# Sheet1.net
KiCad netlist of a schematic drawn in Altium Designer
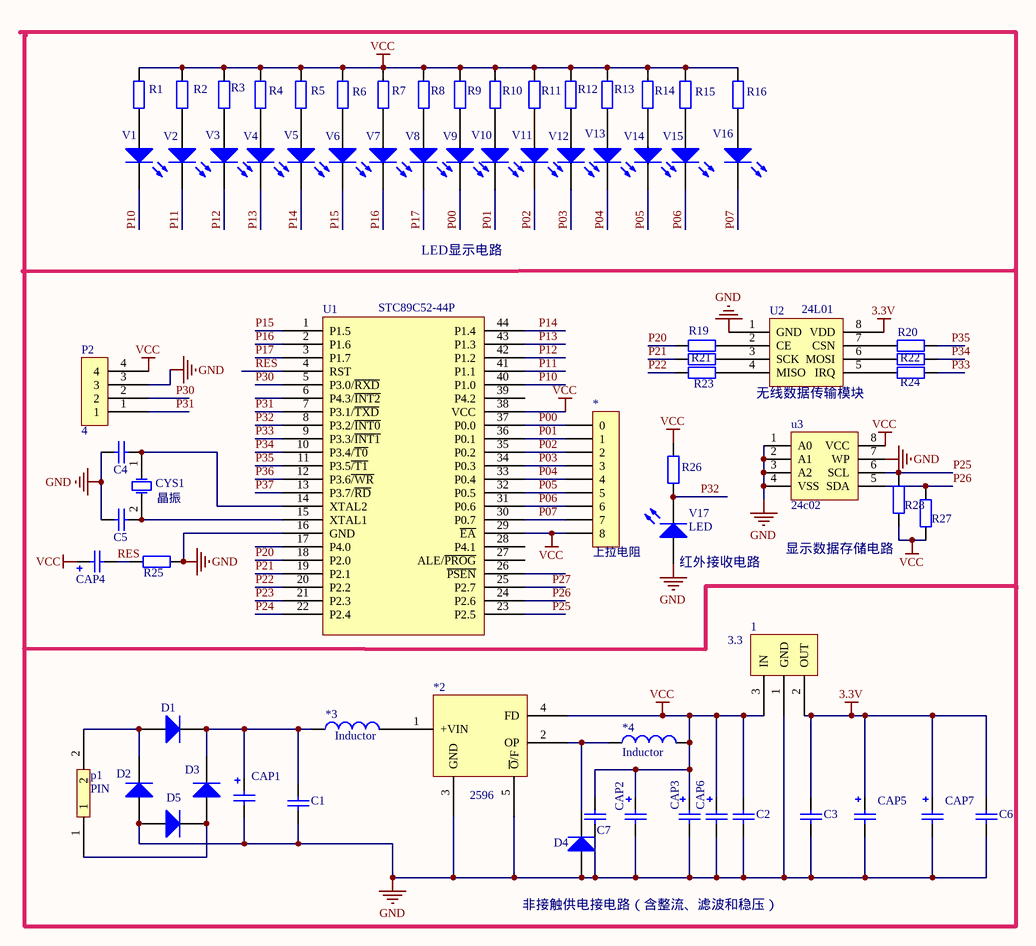
[diagram p0: Sheet1.SchDoc]

(export (version "E")
  (design (tool "Eeschema 10.0.6"))
  (components
    (comp (ref "*") (value "上拉电阻") (footprint "上拉电阻") (libsource (lib "标准封装") (part "上拉电阻")))
    (comp (ref "*2") (value "2596") (footprint "LM2596-P") (libsource (lib "标准封装") (part "2596")))
    (comp (ref "*3") (value "Inductor") (footprint "PIN") (libsource (lib "标准封装") (part "Inductor")))
    (comp (ref "*4") (value "Inductor") (footprint "PIN") (libsource (lib "标准封装") (part "Inductor")))
    (comp (ref "1") (value "3.3") (footprint "3.3") (libsource (lib "标准封装") (part "3.3")))
    (comp (ref "C1") (value "Cap") (footprint "RES") (libsource (lib "标准封装") (part "Cap")))
    (comp (ref "C2") (value "Cap") (footprint "C - duplicate") (libsource (lib "标准封装") (part "Cap")))
    (comp (ref "C3") (value "Cap") (footprint "C - duplicate") (libsource (lib "标准封装") (part "Cap")))
    (comp (ref "C4") (value "Cap") (footprint "C - duplicate") (libsource (lib "标准封装") (part "Cap")))
    (comp (ref "C5") (value "Cap") (footprint "C - duplicate") (libsource (lib "标准封装") (part "Cap")))
    (comp (ref "C6") (value "Cap") (footprint "C - duplicate") (libsource (lib "标准封装") (part "Cap")))
    (comp (ref "C7") (value "Cap") (footprint "C - duplicate") (libsource (lib "标准封装") (part "Cap")))
    (comp (ref "CAP1") (value "电解小电容") (footprint "C") (libsource (lib "标准封装") (part "电解小电容")))
    (comp (ref "CAP2") (value "电解小电容") (footprint "C") (libsource (lib "标准封装") (part "电解小电容")))
    (comp (ref "CAP3") (value "电解小电容") (footprint "CAP - duplicate") (libsource (lib "标准封装") (part "电解小电容")))
    (comp (ref "CAP4") (value "电解小电容") (footprint "CAP - duplicate") (libsource (lib "标准封装") (part "电解小电容")))
    (comp (ref "CAP5") (value "电解小电容") (footprint "CAP - duplicate") (libsource (lib "标准封装") (part "电解小电容")))
    (comp (ref "CAP6") (value "电解小电容") (footprint "CAP - duplicate") (libsource (lib "标准封装") (part "电解小电容")))
    (comp (ref "CAP7") (value "电解小电容") (footprint "电解小电容") (libsource (lib "标准封装") (part "电解小电容")))
    (comp (ref "CYS1") (value "晶振") (footprint "晶振-p") (libsource (lib "标准封装") (part "晶振")))
    (comp (ref "D1") (value "二极管") (footprint "IN4148") (libsource (lib "标准封装") (part "二极管")))
    (comp (ref "D2") (value "二极管") (footprint "IN4148") (libsource (lib "标准封装") (part "二极管")))
    (comp (ref "D3") (value "二极管") (footprint "IN4148") (libsource (lib "标准封装") (part "二极管")))
    (comp (ref "D4") (value "二极管") (footprint "1N4001") (libsource (lib "标准封装") (part "二极管")))
    (comp (ref "D5") (value "二极管") (footprint "IN4148") (libsource (lib "标准封装") (part "二极管")))
    (comp (ref "p1") (value "PIN") (footprint "PIN") (libsource (lib "标准封装") (part "PIN")))
    (comp (ref "P2") (value "4") (footprint "4") (libsource (lib "标准封装") (part "4")))
    (comp (ref "R1") (value "电阻") (footprint "C - duplicate") (libsource (lib "标准封装") (part "电阻")))
    (comp (ref "R2") (value "电阻") (footprint "C - duplicate") (libsource (lib "标准封装") (part "电阻")))
    (comp (ref "R3") (value "电阻") (footprint "C - duplicate") (libsource (lib "标准封装") (part "电阻")))
    (comp (ref "R4") (value "电阻") (footprint "C - duplicate") (libsource (lib "标准封装") (part "电阻")))
    (comp (ref "R5") (value "电阻") (footprint "C - duplicate") (libsource (lib "标准封装") (part "电阻")))
    (comp (ref "R6") (value "电阻") (footprint "C - duplicate") (libsource (lib "标准封装") (part "电阻")))
    (comp (ref "R7") (value "电阻") (footprint "C - duplicate") (libsource (lib "标准封装") (part "电阻")))
    (comp (ref "R8") (value "电阻") (footprint "C - duplicate") (libsource (lib "标准封装") (part "电阻")))
    (comp (ref "R9") (value "电阻") (footprint "C - duplicate") (libsource (lib "标准封装") (part "电阻")))
    (comp (ref "R10") (value "电阻") (footprint "C - duplicate") (libsource (lib "标准封装") (part "电阻")))
    (comp (ref "R11") (value "电阻") (footprint "C - duplicate") (libsource (lib "标准封装") (part "电阻")))
    (comp (ref "R12") (value "电阻") (footprint "C - duplicate") (libsource (lib "标准封装") (part "电阻")))
    (comp (ref "R13") (value "电阻") (footprint "C - duplicate") (libsource (lib "标准封装") (part "电阻")))
    (comp (ref "R14") (value "电阻") (footprint "C - duplicate") (libsource (lib "标准封装") (part "电阻")))
    (comp (ref "R15") (value "电阻") (footprint "C - duplicate") (libsource (lib "标准封装") (part "电阻")))
    (comp (ref "R16") (value "电阻") (footprint "C - duplicate") (libsource (lib "标准封装") (part "电阻")))
    (comp (ref "R19") (value "电阻") (footprint "C - duplicate") (libsource (lib "") (part "电阻_2")))
    (comp (ref "R20") (value "电阻") (footprint "C - duplicate") (libsource (lib "") (part "电阻_2")))
    (comp (ref "R21") (value "电阻") (footprint "C - duplicate") (libsource (lib "") (part "电阻_2")))
    (comp (ref "R22") (value "电阻") (footprint "C - duplicate") (libsource (lib "") (part "电阻_2")))
    (comp (ref "R23") (value "电阻") (footprint "C - duplicate") (libsource (lib "") (part "电阻_2")))
    (comp (ref "R24") (value "电阻") (footprint "C - duplicate") (libsource (lib "") (part "电阻_2")))
    (comp (ref "R25") (value "电阻") (footprint "C - duplicate") (libsource (lib "") (part "电阻_3")))
    (comp (ref "R26") (value "电阻") (footprint "RES") (libsource (lib "") (part "电阻_1")))
    (comp (ref "R27") (value "电阻") (footprint "RES") (libsource (lib "") (part "电阻_1")))
    (comp (ref "R28") (value "电阻") (footprint "RES") (libsource (lib "") (part "电阻_1")))
    (comp (ref "U1")
      (value "STC89C52-44P")
      (footprint "LCC44 - duplicate")
      (libsource (lib "标准封装") (part "STC89C52-44P"))
    )
    (comp (ref "U2") (value "24L01") (footprint "24L01") (libsource (lib "标准封装") (part "24L01")))
    (comp (ref "u3") (value "24c02") (footprint "24C02") (libsource (lib "标准封装") (part "24c02")))
    (comp (ref "V1") (value "LED") (footprint "C - duplicate") (libsource (lib "标准封装") (part "LED")))
    (comp (ref "V2") (value "LED") (footprint "C - duplicate") (libsource (lib "标准封装") (part "LED")))
    (comp (ref "V3") (value "LED") (footprint "C - duplicate") (libsource (lib "标准封装") (part "LED")))
    (comp (ref "V4") (value "LED") (footprint "C - duplicate") (libsource (lib "标准封装") (part "LED")))
    (comp (ref "V5") (value "LED") (footprint "C - duplicate") (libsource (lib "标准封装") (part "LED")))
    (comp (ref "V6") (value "LED") (footprint "C - duplicate") (libsource (lib "标准封装") (part "LED")))
    (comp (ref "V7") (value "LED") (footprint "C - duplicate") (libsource (lib "标准封装") (part "LED")))
    (comp (ref "V8") (value "LED") (footprint "C - duplicate") (libsource (lib "标准封装") (part "LED")))
    (comp (ref "V9") (value "LED") (footprint "C - duplicate") (libsource (lib "标准封装") (part "LED")))
    (comp (ref "V10") (value "LED") (footprint "C - duplicate") (libsource (lib "标准封装") (part "LED")))
    (comp (ref "V11") (value "LED") (footprint "C - duplicate") (libsource (lib "标准封装") (part "LED")))
    (comp (ref "V12") (value "LED") (footprint "C - duplicate") (libsource (lib "标准封装") (part "LED")))
    (comp (ref "V13") (value "LED") (footprint "C - duplicate") (libsource (lib "标准封装") (part "LED")))
    (comp (ref "V14") (value "LED") (footprint "C - duplicate") (libsource (lib "标准封装") (part "LED")))
    (comp (ref "V15") (value "LED") (footprint "C - duplicate") (libsource (lib "标准封装") (part "LED")))
    (comp (ref "V16") (value "LED") (footprint "C - duplicate") (libsource (lib "标准封装") (part "LED")))
    (comp (ref "V17") (value "LED") (footprint "LED") (libsource (lib "标准封装") (part "LED")))
  )
  (nets
    (net (code "1") (name "/P00") (class "Default")
      (node (ref "*") (pin "0") (pinfunction "0_0") (pintype "passive"))
      (node (ref "U1") (pin "37") (pinfunction "P0.0_37") (pintype "passive"))
      (node (ref "V9") (pin "2") (pinfunction "K_2") (pintype "passive"))
    )
    (net (code "2") (name "/P01") (class "Default")
      (node (ref "*") (pin "1") (pinfunction "1_1") (pintype "passive"))
      (node (ref "U1") (pin "36") (pinfunction "P0.1_36") (pintype "passive"))
      (node (ref "V10") (pin "2") (pinfunction "K_2") (pintype "passive"))
    )
    (net (code "3") (name "/P02") (class "Default")
      (node (ref "*") (pin "2") (pinfunction "2_2") (pintype "passive"))
      (node (ref "U1") (pin "35") (pinfunction "P0.2_35") (pintype "passive"))
      (node (ref "V11") (pin "2") (pinfunction "K_2") (pintype "passive"))
    )
    (net (code "4") (name "/P03") (class "Default")
      (node (ref "*") (pin "3") (pinfunction "3_3") (pintype "passive"))
      (node (ref "U1") (pin "34") (pinfunction "P0.3_34") (pintype "passive"))
      (node (ref "V12") (pin "2") (pinfunction "K_2") (pintype "passive"))
    )
    (net (code "5") (name "/P04") (class "Default")
      (node (ref "*") (pin "4") (pinfunction "4_4") (pintype "passive"))
      (node (ref "U1") (pin "33") (pinfunction "P0.4_33") (pintype "passive"))
      (node (ref "V13") (pin "2") (pinfunction "K_2") (pintype "passive"))
    )
    (net (code "6") (name "/P05") (class "Default")
      (node (ref "*") (pin "5") (pinfunction "5_5") (pintype "passive"))
      (node (ref "U1") (pin "32") (pinfunction "P0.5_32") (pintype "passive"))
      (node (ref "V14") (pin "2") (pinfunction "K_2") (pintype "passive"))
    )
    (net (code "7") (name "/P06") (class "Default")
      (node (ref "*") (pin "6") (pinfunction "6_6") (pintype "passive"))
      (node (ref "U1") (pin "31") (pinfunction "P0.6_31") (pintype "passive"))
      (node (ref "V15") (pin "2") (pinfunction "K_2") (pintype "passive"))
    )
    (net (code "8") (name "/P07") (class "Default")
      (node (ref "*") (pin "7") (pinfunction "7_7") (pintype "passive"))
      (node (ref "U1") (pin "30") (pinfunction "P0.7_30") (pintype "passive"))
      (node (ref "V16") (pin "2") (pinfunction "K_2") (pintype "passive"))
    )
    (net (code "9") (name "/P10") (class "Default")
      (node (ref "U1") (pin "40") (pinfunction "P1.0_40") (pintype "passive"))
      (node (ref "V1") (pin "2") (pinfunction "K_2") (pintype "passive"))
    )
    (net (code "10") (name "/P11") (class "Default")
      (node (ref "U1") (pin "41") (pinfunction "P1.1_41") (pintype "passive"))
      (node (ref "V2") (pin "2") (pinfunction "K_2") (pintype "passive"))
    )
    (net (code "11") (name "/P12") (class "Default")
      (node (ref "U1") (pin "42") (pinfunction "P1.2_42") (pintype "passive"))
      (node (ref "V3") (pin "2") (pinfunction "K_2") (pintype "passive"))
    )
    (net (code "12") (name "/P13") (class "Default")
      (node (ref "U1") (pin "43") (pinfunction "P1.3_43") (pintype "passive"))
      (node (ref "V4") (pin "2") (pinfunction "K_2") (pintype "passive"))
    )
    (net (code "13") (name "/P14") (class "Default")
      (node (ref "U1") (pin "44") (pinfunction "P1.4_44") (pintype "passive"))
      (node (ref "V5") (pin "2") (pinfunction "K_2") (pintype "passive"))
    )
    (net (code "14") (name "/P15") (class "Default")
      (node (ref "U1") (pin "1") (pinfunction "P1.5_1") (pintype "passive"))
      (node (ref "V6") (pin "2") (pinfunction "K_2") (pintype "passive"))
    )
    (net (code "15") (name "/P16") (class "Default")
      (node (ref "U1") (pin "2") (pinfunction "P1.6_2") (pintype "passive"))
      (node (ref "V7") (pin "2") (pinfunction "K_2") (pintype "passive"))
    )
    (net (code "16") (name "/P17") (class "Default")
      (node (ref "U1") (pin "3") (pinfunction "P1.7_3") (pintype "passive"))
      (node (ref "V8") (pin "2") (pinfunction "K_2") (pintype "passive"))
    )
    (net (code "17") (name "/P20") (class "Default")
      (node (ref "R19") (pin "2") (pinfunction "2_2") (pintype "passive"))
      (node (ref "U1") (pin "18") (pinfunction "P2.0_18") (pintype "passive"))
    )
    (net (code "18") (name "/P21") (class "Default")
      (node (ref "R21") (pin "2") (pinfunction "2_2") (pintype "passive"))
      (node (ref "U1") (pin "19") (pinfunction "P2.1_19") (pintype "passive"))
    )
    (net (code "19") (name "/P22") (class "Default")
      (node (ref "R23") (pin "2") (pinfunction "2_2") (pintype "passive"))
      (node (ref "U1") (pin "20") (pinfunction "P2.2_20") (pintype "passive"))
    )
    (net (code "20") (name "/P23") (class "Default")
      (node (ref "U1") (pin "21") (pinfunction "P2.3_21") (pintype "passive"))
    )
    (net (code "21") (name "/P24") (class "Default")
      (node (ref "U1") (pin "22") (pinfunction "P2.4_22") (pintype "passive"))
    )
    (net (code "22") (name "/P25") (class "Default")
      (node (ref "R28") (pin "1") (pinfunction "1_1") (pintype "passive"))
      (node (ref "U1") (pin "23") (pinfunction "P2.5_23") (pintype "passive"))
      (node (ref "u3") (pin "6") (pinfunction "SCL_6") (pintype "passive"))
    )
    (net (code "23") (name "/P26") (class "Default")
      (node (ref "R27") (pin "1") (pinfunction "1_1") (pintype "passive"))
      (node (ref "U1") (pin "24") (pinfunction "P2.6_24") (pintype "passive"))
      (node (ref "u3") (pin "5") (pinfunction "SDA_5") (pintype "passive"))
    )
    (net (code "24") (name "/P27") (class "Default")
      (node (ref "U1") (pin "25") (pinfunction "P2.7_25") (pintype "passive"))
    )
    (net (code "25") (name "/P30") (class "Default")
      (node (ref "P2") (pin "2") (pinfunction "2_2") (pintype "passive"))
      (node (ref "U1") (pin "5") (pinfunction "P3.0/~{RXD}_5") (pintype "passive"))
    )
    (net (code "26") (name "/P31") (class "Default")
      (node (ref "P2") (pin "1") (pinfunction "1_1") (pintype "passive"))
      (node (ref "U1") (pin "7") (pinfunction "P3.1/~{TXD}_7") (pintype "passive"))
    )
    (net (code "27") (name "/P32") (class "Default")
      (node (ref "R26") (pin "2") (pinfunction "2_2") (pintype "passive"))
      (node (ref "U1") (pin "8") (pinfunction "P3.2/~{INT0}_8") (pintype "passive"))
      (node (ref "V17") (pin "2") (pinfunction "K_2") (pintype "passive"))
    )
    (net (code "28") (name "/P33") (class "Default")
      (node (ref "R24") (pin "1") (pinfunction "1_1") (pintype "passive"))
      (node (ref "U1") (pin "9") (pinfunction "P3.3/~{INT1}_9") (pintype "passive"))
    )
    (net (code "29") (name "/P34") (class "Default")
      (node (ref "R22") (pin "1") (pinfunction "1_1") (pintype "passive"))
      (node (ref "U1") (pin "10") (pinfunction "P3.4/~{T0}_10") (pintype "passive"))
    )
    (net (code "30") (name "/P35") (class "Default")
      (node (ref "R20") (pin "1") (pinfunction "1_1") (pintype "passive"))
      (node (ref "U1") (pin "11") (pinfunction "P3.5~{/T1}_11") (pintype "passive"))
    )
    (net (code "31") (name "/P36") (class "Default")
      (node (ref "U1") (pin "12") (pinfunction "P3.6~{/WR}_12") (pintype "passive"))
    )
    (net (code "32") (name "/P37") (class "Default")
      (node (ref "U1") (pin "13") (pinfunction "P3.7/~{RD}_13") (pintype "passive"))
    )
    (net (code "33") (name "/RES") (class "Default")
      (node (ref "CAP4") (pin "1") (pinfunction "1_1") (pintype "passive"))
      (node (ref "R25") (pin "1") (pinfunction "1_1") (pintype "passive"))
      (node (ref "U1") (pin "4") (pinfunction "RST_4") (pintype "passive"))
    )
    (net (code "34") (name "3.3V") (class "Default")
      (node (ref "1") (pin "2") (pinfunction "OUT_2") (pintype "passive"))
      (node (ref "C3") (pin "2") (pinfunction "2_2") (pintype "passive"))
      (node (ref "C6") (pin "2") (pinfunction "2_2") (pintype "passive"))
      (node (ref "CAP5") (pin "2") (pinfunction "2_2") (pintype "passive"))
      (node (ref "CAP7") (pin "2") (pinfunction "2_2") (pintype "passive"))
      (node (ref "U2") (pin "8") (pinfunction "VDD_8") (pintype "passive"))
    )
    (net (code "35") (name "GND") (class "Default")
      (node (ref "*2") (pin "3") (pinfunction "GND_3") (pintype "passive"))
      (node (ref "*2") (pin "5") (pinfunction "~{O}/F_5") (pintype "passive"))
      (node (ref "1") (pin "1") (pinfunction "GND_1") (pintype "passive"))
      (node (ref "C1") (pin "1") (pinfunction "1_1") (pintype "passive"))
      (node (ref "C2") (pin "1") (pinfunction "1_1") (pintype "passive"))
      (node (ref "C3") (pin "1") (pinfunction "1_1") (pintype "passive"))
      (node (ref "C4") (pin "2") (pinfunction "2_2") (pintype "passive"))
      (node (ref "C5") (pin "2") (pinfunction "2_2") (pintype "passive"))
      (node (ref "C6") (pin "1") (pinfunction "1_1") (pintype "passive"))
      (node (ref "C7") (pin "1") (pinfunction "1_1") (pintype "passive"))
      (node (ref "CAP1") (pin "1") (pinfunction "1_1") (pintype "passive"))
      (node (ref "CAP2") (pin "1") (pinfunction "1_1") (pintype "passive"))
      (node (ref "CAP3") (pin "1") (pinfunction "1_1") (pintype "passive"))
      (node (ref "CAP5") (pin "1") (pinfunction "1_1") (pintype "passive"))
      (node (ref "CAP6") (pin "1") (pinfunction "1_1") (pintype "passive"))
      (node (ref "CAP7") (pin "1") (pinfunction "1_1") (pintype "passive"))
      (node (ref "D2") (pin "1") (pinfunction "A_1") (pintype "passive"))
      (node (ref "D4") (pin "1") (pinfunction "A_1") (pintype "passive"))
      (node (ref "D5") (pin "1") (pinfunction "A_1") (pintype "passive"))
      (node (ref "P2") (pin "3") (pinfunction "3_3") (pintype "passive"))
      (node (ref "R25") (pin "2") (pinfunction "2_2") (pintype "passive"))
      (node (ref "U1") (pin "16") (pinfunction "GND_16") (pintype "passive"))
      (node (ref "U2") (pin "1") (pinfunction "GND_1") (pintype "passive"))
      (node (ref "V17") (pin "1") (pinfunction "A_1") (pintype "passive"))
      (node (ref "u3") (pin "1") (pinfunction "A0_1") (pintype "passive"))
      (node (ref "u3") (pin "2") (pinfunction "A1_2") (pintype "passive"))
      (node (ref "u3") (pin "3") (pinfunction "A2_3") (pintype "passive"))
      (node (ref "u3") (pin "4") (pinfunction "VSS_4") (pintype "passive"))
      (node (ref "u3") (pin "7") (pinfunction "WP_7") (pintype "passive"))
    )
    (net (code "36") (name "Net-(*2-+VIN)") (class "Default")
      (node (ref "*2") (pin "1") (pinfunction "+VIN_1") (pintype "passive"))
      (node (ref "*3") (pin "2") (pinfunction "2_2") (pintype "passive"))
    )
    (net (code "37") (name "Net-(*2-OP)") (class "Default")
      (node (ref "*2") (pin "2") (pinfunction "OP_2") (pintype "passive"))
      (node (ref "*4") (pin "1") (pinfunction "1_1") (pintype "passive"))
      (node (ref "D4") (pin "2") (pinfunction "K_2") (pintype "passive"))
    )
    (net (code "38") (name "Net-(D1-A)") (class "Default")
      (node (ref "D1") (pin "1") (pinfunction "A_1") (pintype "passive"))
      (node (ref "D2") (pin "2") (pinfunction "K_2") (pintype "passive"))
      (node (ref "p1") (pin "2") (pinfunction "2_2") (pintype "passive"))
    )
    (net (code "39") (name "Net-(D1-K)") (class "Default")
      (node (ref "*3") (pin "1") (pinfunction "1_1") (pintype "passive"))
      (node (ref "C1") (pin "2") (pinfunction "2_2") (pintype "passive"))
      (node (ref "CAP1") (pin "2") (pinfunction "2_2") (pintype "passive"))
      (node (ref "D1") (pin "2") (pinfunction "K_2") (pintype "passive"))
      (node (ref "D3") (pin "2") (pinfunction "K_2") (pintype "passive"))
    )
    (net (code "40") (name "Net-(D3-A)") (class "Default")
      (node (ref "D3") (pin "1") (pinfunction "A_1") (pintype "passive"))
      (node (ref "D5") (pin "2") (pinfunction "K_2") (pintype "passive"))
      (node (ref "p1") (pin "1") (pinfunction "1_1") (pintype "passive"))
    )
    (net (code "41") (name "Net-(U1-XTAL1)") (class "Default")
      (node (ref "C5") (pin "1") (pinfunction "1_1") (pintype "passive"))
      (node (ref "CYS1") (pin "2") (pinfunction "CRYSTAL_2") (pintype "passive"))
      (node (ref "U1") (pin "15") (pinfunction "XTAL1_15") (pintype "passive"))
    )
    (net (code "42") (name "Net-(U1-XTAL2)") (class "Default")
      (node (ref "C4") (pin "1") (pinfunction "1_1") (pintype "passive"))
      (node (ref "CYS1") (pin "1") (pinfunction "CRYSTAL_1") (pintype "passive"))
      (node (ref "U1") (pin "14") (pinfunction "XTAL2_14") (pintype "passive"))
    )
    (net (code "43") (name "Net-(U2-CE)") (class "Default")
      (node (ref "R19") (pin "1") (pinfunction "1_1") (pintype "passive"))
      (node (ref "U2") (pin "2") (pinfunction "CE_2") (pintype "passive"))
    )
    (net (code "44") (name "Net-(U2-CSN)") (class "Default")
      (node (ref "R20") (pin "2") (pinfunction "2_2") (pintype "passive"))
      (node (ref "U2") (pin "7") (pinfunction "CSN_7") (pintype "passive"))
    )
    (net (code "45") (name "Net-(U2-IRQ)") (class "Default")
      (node (ref "R24") (pin "2") (pinfunction "2_2") (pintype "passive"))
      (node (ref "U2") (pin "5") (pinfunction "IRQ_5") (pintype "passive"))
    )
    (net (code "46") (name "Net-(U2-MISO)") (class "Default")
      (node (ref "R23") (pin "1") (pinfunction "1_1") (pintype "passive"))
      (node (ref "U2") (pin "4") (pinfunction "MISO_4") (pintype "passive"))
    )
    (net (code "47") (name "Net-(U2-MOSI)") (class "Default")
      (node (ref "R22") (pin "2") (pinfunction "2_2") (pintype "passive"))
      (node (ref "U2") (pin "6") (pinfunction "MOSI_6") (pintype "passive"))
    )
    (net (code "48") (name "Net-(U2-SCK)") (class "Default")
      (node (ref "R21") (pin "1") (pinfunction "1_1") (pintype "passive"))
      (node (ref "U2") (pin "3") (pinfunction "SCK_3") (pintype "passive"))
    )
    (net (code "49") (name "Net-(V1-A)") (class "Default")
      (node (ref "R1") (pin "1") (pinfunction "1_1") (pintype "passive"))
      (node (ref "V1") (pin "1") (pinfunction "A_1") (pintype "passive"))
    )
    (net (code "50") (name "Net-(V2-A)") (class "Default")
      (node (ref "R2") (pin "1") (pinfunction "1_1") (pintype "passive"))
      (node (ref "V2") (pin "1") (pinfunction "A_1") (pintype "passive"))
    )
    (net (code "51") (name "Net-(V3-A)") (class "Default")
      (node (ref "R3") (pin "1") (pinfunction "1_1") (pintype "passive"))
      (node (ref "V3") (pin "1") (pinfunction "A_1") (pintype "passive"))
    )
    (net (code "52") (name "Net-(V4-A)") (class "Default")
      (node (ref "R4") (pin "1") (pinfunction "1_1") (pintype "passive"))
      (node (ref "V4") (pin "1") (pinfunction "A_1") (pintype "passive"))
    )
    (net (code "53") (name "Net-(V5-A)") (class "Default")
      (node (ref "R5") (pin "1") (pinfunction "1_1") (pintype "passive"))
      (node (ref "V5") (pin "1") (pinfunction "A_1") (pintype "passive"))
    )
    (net (code "54") (name "Net-(V6-A)") (class "Default")
      (node (ref "R6") (pin "1") (pinfunction "1_1") (pintype "passive"))
      (node (ref "V6") (pin "1") (pinfunction "A_1") (pintype "passive"))
    )
    (net (code "55") (name "Net-(V7-A)") (class "Default")
      (node (ref "R7") (pin "1") (pinfunction "1_1") (pintype "passive"))
      (node (ref "V7") (pin "1") (pinfunction "A_1") (pintype "passive"))
    )
    (net (code "56") (name "Net-(V8-A)") (class "Default")
      (node (ref "R8") (pin "1") (pinfunction "1_1") (pintype "passive"))
      (node (ref "V8") (pin "1") (pinfunction "A_1") (pintype "passive"))
    )
    (net (code "57") (name "Net-(V9-A)") (class "Default")
      (node (ref "R9") (pin "1") (pinfunction "1_1") (pintype "passive"))
      (node (ref "V9") (pin "1") (pinfunction "A_1") (pintype "passive"))
    )
    (net (code "58") (name "Net-(V10-A)") (class "Default")
      (node (ref "R10") (pin "1") (pinfunction "1_1") (pintype "passive"))
      (node (ref "V10") (pin "1") (pinfunction "A_1") (pintype "passive"))
    )
    (net (code "59") (name "Net-(V11-A)") (class "Default")
      (node (ref "R11") (pin "1") (pinfunction "1_1") (pintype "passive"))
      (node (ref "V11") (pin "1") (pinfunction "A_1") (pintype "passive"))
    )
    (net (code "60") (name "Net-(V12-A)") (class "Default")
      (node (ref "R12") (pin "1") (pinfunction "1_1") (pintype "passive"))
      (node (ref "V12") (pin "1") (pinfunction "A_1") (pintype "passive"))
    )
    (net (code "61") (name "Net-(V13-A)") (class "Default")
      (node (ref "R13") (pin "1") (pinfunction "1_1") (pintype "passive"))
      (node (ref "V13") (pin "1") (pinfunction "A_1") (pintype "passive"))
    )
    (net (code "62") (name "Net-(V14-A)") (class "Default")
      (node (ref "R14") (pin "1") (pinfunction "1_1") (pintype "passive"))
      (node (ref "V14") (pin "1") (pinfunction "A_1") (pintype "passive"))
    )
    (net (code "63") (name "Net-(V15-A)") (class "Default")
      (node (ref "R15") (pin "1") (pinfunction "1_1") (pintype "passive"))
      (node (ref "V15") (pin "1") (pinfunction "A_1") (pintype "passive"))
    )
    (net (code "64") (name "Net-(V16-A)") (class "Default")
      (node (ref "R16") (pin "1") (pinfunction "1_1") (pintype "passive"))
      (node (ref "V16") (pin "1") (pinfunction "A_1") (pintype "passive"))
    )
    (net (code "65") (name "VCC") (class "Default")
      (node (ref "*") (pin "8") (pinfunction "8_8") (pintype "passive"))
      (node (ref "*2") (pin "4") (pinfunction "FD_4") (pintype "passive"))
      (node (ref "*4") (pin "2") (pinfunction "2_2") (pintype "passive"))
      (node (ref "1") (pin "3") (pinfunction "IN_3") (pintype "passive"))
      (node (ref "C2") (pin "2") (pinfunction "2_2") (pintype "passive"))
      (node (ref "C7") (pin "2") (pinfunction "2_2") (pintype "passive"))
      (node (ref "CAP2") (pin "2") (pinfunction "2_2") (pintype "passive"))
      (node (ref "CAP3") (pin "2") (pinfunction "2_2") (pintype "passive"))
      (node (ref "CAP4") (pin "2") (pinfunction "2_2") (pintype "passive"))
      (node (ref "CAP6") (pin "2") (pinfunction "2_2") (pintype "passive"))
      (node (ref "P2") (pin "4") (pinfunction "4_4") (pintype "passive"))
      (node (ref "R1") (pin "2") (pinfunction "2_2") (pintype "passive"))
      (node (ref "R10") (pin "2") (pinfunction "2_2") (pintype "passive"))
      (node (ref "R11") (pin "2") (pinfunction "2_2") (pintype "passive"))
      (node (ref "R12") (pin "2") (pinfunction "2_2") (pintype "passive"))
      (node (ref "R13") (pin "2") (pinfunction "2_2") (pintype "passive"))
      (node (ref "R14") (pin "2") (pinfunction "2_2") (pintype "passive"))
      (node (ref "R15") (pin "2") (pinfunction "2_2") (pintype "passive"))
      (node (ref "R16") (pin "2") (pinfunction "2_2") (pintype "passive"))
      (node (ref "R2") (pin "2") (pinfunction "2_2") (pintype "passive"))
      (node (ref "R26") (pin "1") (pinfunction "1_1") (pintype "passive"))
      (node (ref "R27") (pin "2") (pinfunction "2_2") (pintype "passive"))
      (node (ref "R28") (pin "2") (pinfunction "2_2") (pintype "passive"))
      (node (ref "R3") (pin "2") (pinfunction "2_2") (pintype "passive"))
      (node (ref "R4") (pin "2") (pinfunction "2_2") (pintype "passive"))
      (node (ref "R5") (pin "2") (pinfunction "2_2") (pintype "passive"))
      (node (ref "R6") (pin "2") (pinfunction "2_2") (pintype "passive"))
      (node (ref "R7") (pin "2") (pinfunction "2_2") (pintype "passive"))
      (node (ref "R8") (pin "2") (pinfunction "2_2") (pintype "passive"))
      (node (ref "R9") (pin "2") (pinfunction "2_2") (pintype "passive"))
      (node (ref "U1") (pin "29") (pinfunction "~{EA}_29") (pintype "passive"))
      (node (ref "U1") (pin "38") (pinfunction "VCC_38") (pintype "passive"))
      (node (ref "u3") (pin "8") (pinfunction "VCC_8") (pintype "passive"))
    )
    (net (code "66") (name "unconnected-(U1-ALE{slash}~{PROG}-Pad27)") (class "Default")
      (node (ref "U1") (pin "27") (pinfunction "ALE/~{PROG}_27") (pintype "passive"))
    )
    (net (code "67") (name "unconnected-(U1-P4.0-Pad17)") (class "Default")
      (node (ref "U1") (pin "17") (pinfunction "P4.0_17") (pintype "passive"))
    )
    (net (code "68") (name "unconnected-(U1-P4.1-Pad28)") (class "Default")
      (node (ref "U1") (pin "28") (pinfunction "P4.1_28") (pintype "passive"))
    )
    (net (code "69") (name "unconnected-(U1-P4.2-Pad39)") (class "Default")
      (node (ref "U1") (pin "39") (pinfunction "P4.2_39") (pintype "passive"))
    )
    (net (code "70") (name "unconnected-(U1-P4.3{slash}~{INT2}-Pad6)") (class "Default")
      (node (ref "U1") (pin "6") (pinfunction "P4.3/~{INT2}_6") (pintype "passive"))
    )
    (net (code "71") (name "unconnected-(U1-~{PSEN}-Pad26)") (class "Default")
      (node (ref "U1") (pin "26") (pinfunction "~{PSEN}_26") (pintype "passive"))
    )
  )
)
